# WL-BPF_L.net
KiCad netlist of a schematic drawn in Altium Designer
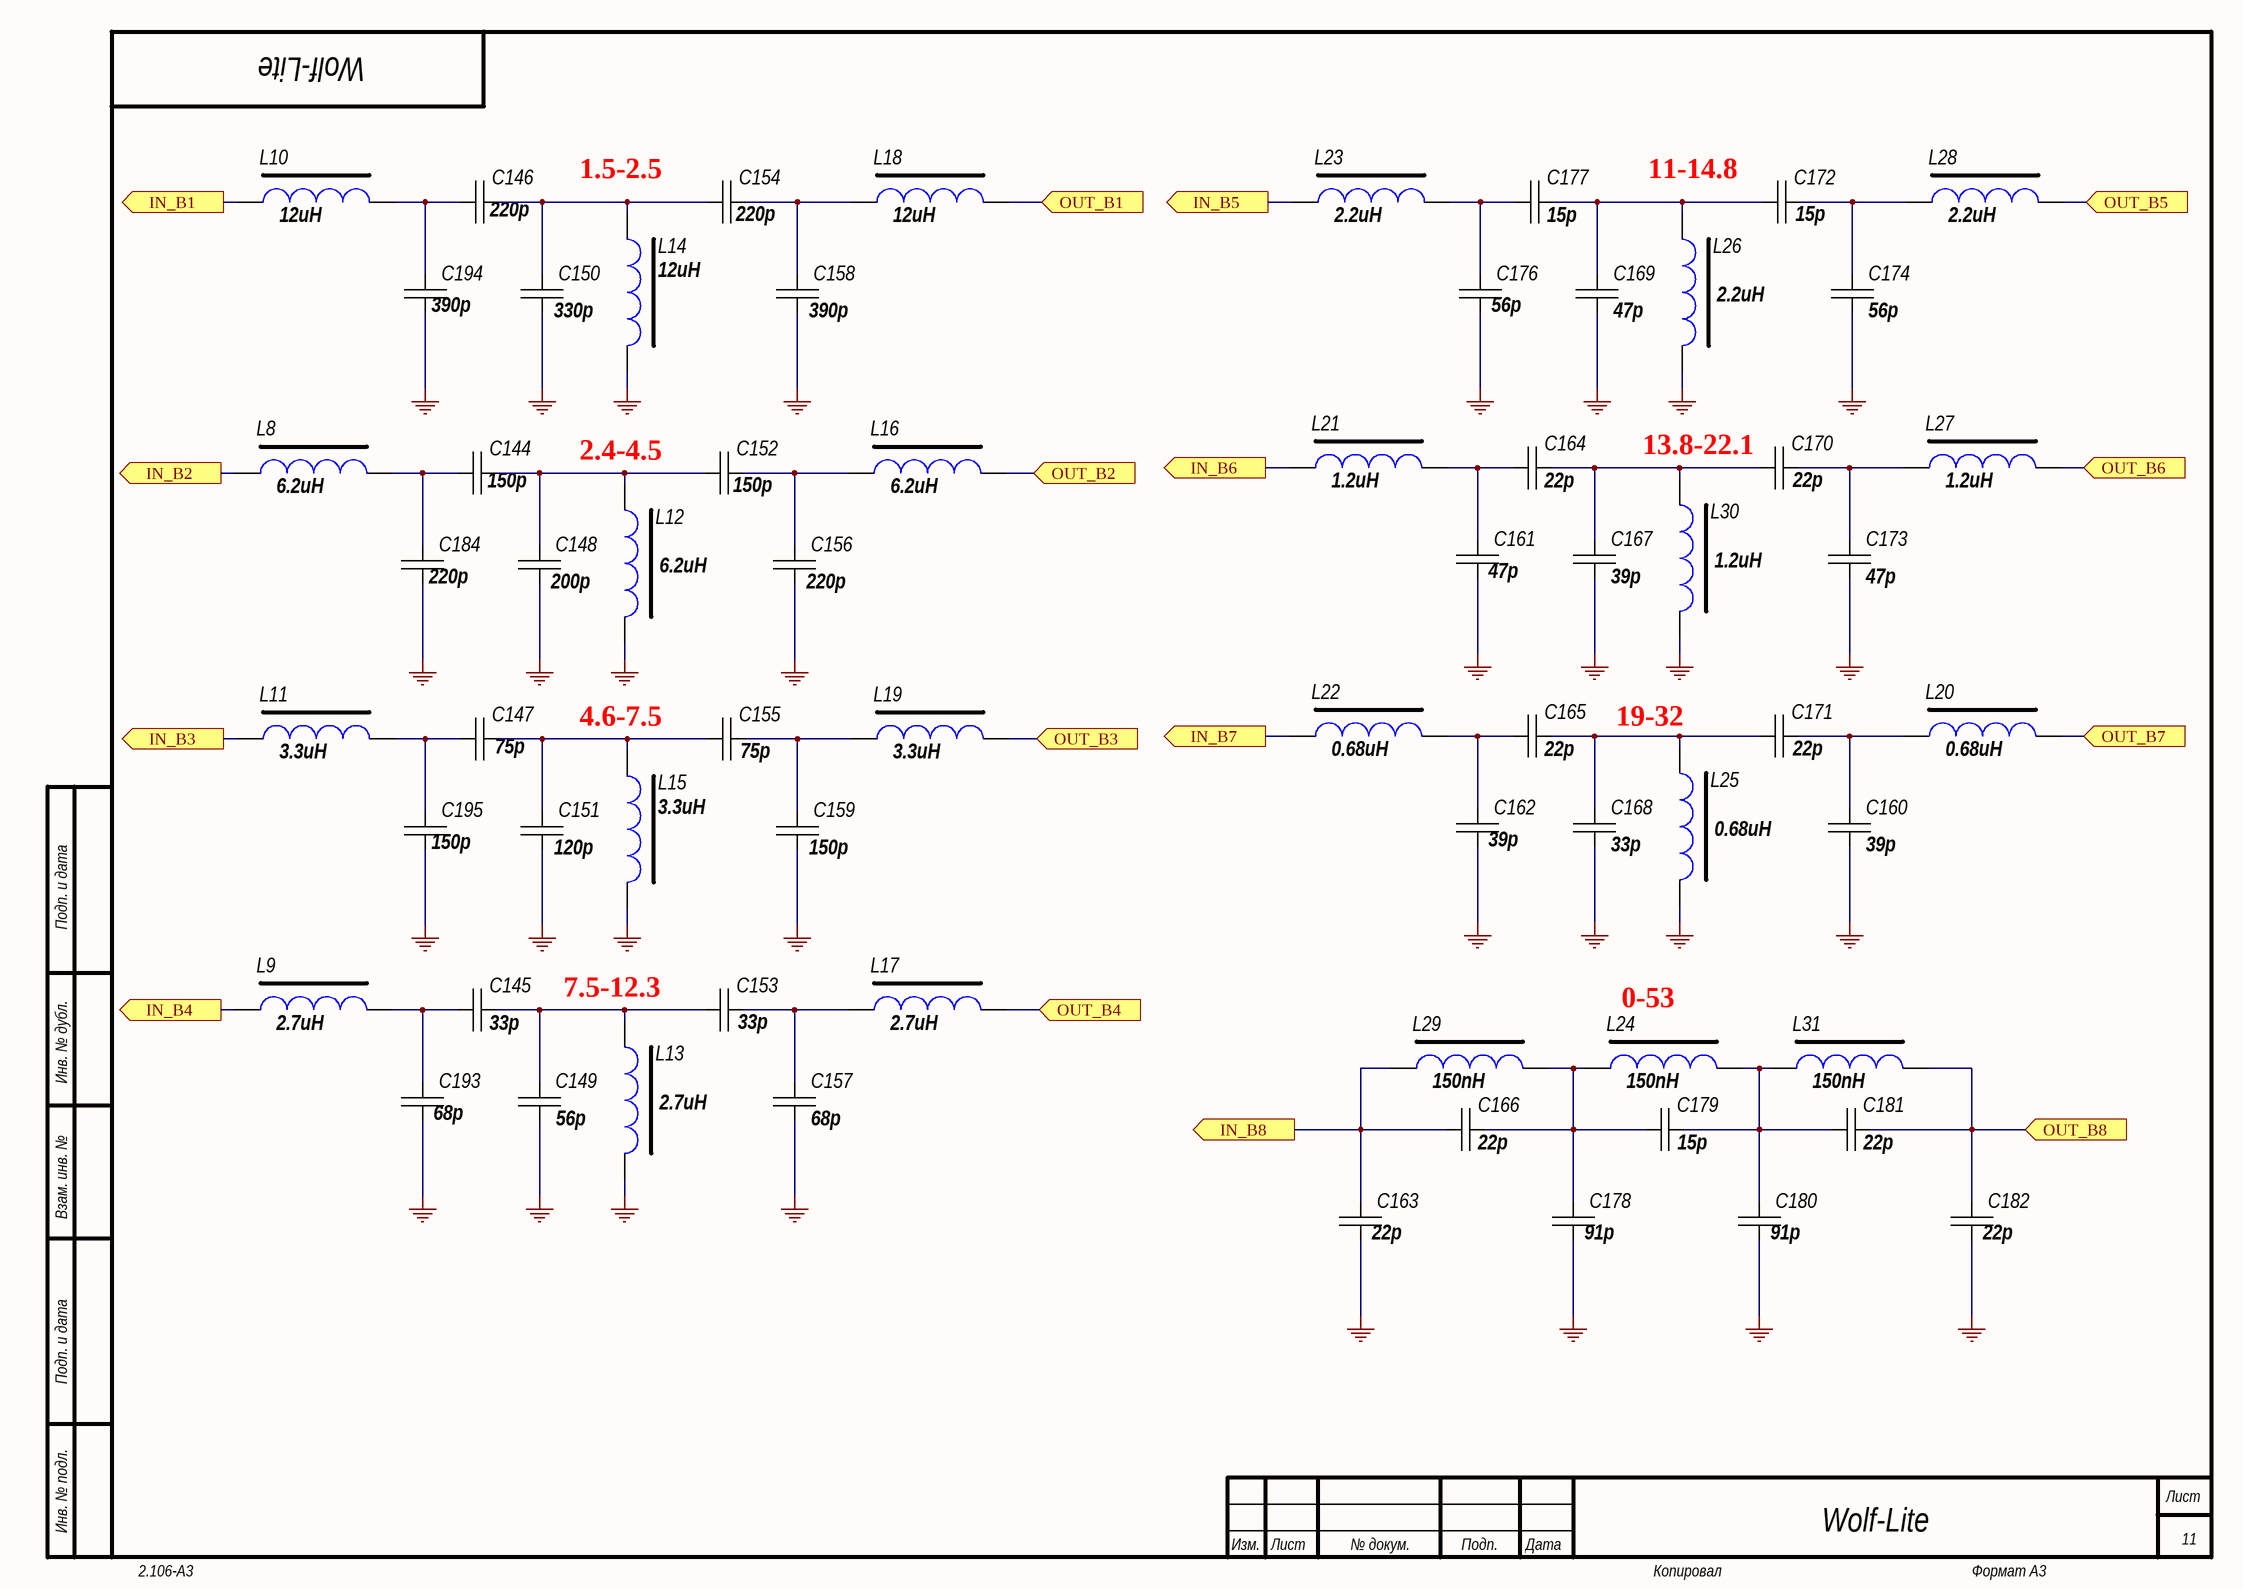
[diagram p0: WL-BPF_L.SchDoc]

(export (version "E")
  (design (tool "Eeschema 10.0.6"))
  (components
    (comp (ref "C144")
      (value "150p")
      (footprint "standard:CH0805C")
      (libsource (lib "Discrete") (part "Capacitor"))
    )
    (comp (ref "C145")
      (value "33p")
      (footprint "standard:CH0805C")
      (libsource (lib "Discrete") (part "Capacitor"))
    )
    (comp (ref "C146")
      (value "220p")
      (footprint "standard:CH0805C")
      (libsource (lib "Discrete") (part "Capacitor"))
    )
    (comp (ref "C147")
      (value "75p")
      (footprint "standard:CH0805C")
      (libsource (lib "Discrete") (part "Capacitor"))
    )
    (comp (ref "C148")
      (value "200p")
      (footprint "standard:CH0805C")
      (libsource (lib "Discrete") (part "Capacitor"))
    )
    (comp (ref "C149")
      (value "56p")
      (footprint "standard:CH0805C")
      (libsource (lib "Discrete") (part "Capacitor"))
    )
    (comp (ref "C150")
      (value "330p")
      (footprint "standard:CH0805C")
      (libsource (lib "Discrete") (part "Capacitor"))
    )
    (comp (ref "C151")
      (value "120p")
      (footprint "standard:CH0805C")
      (libsource (lib "Discrete") (part "Capacitor"))
    )
    (comp (ref "C152")
      (value "150p")
      (footprint "standard:CH0805C")
      (libsource (lib "Discrete") (part "Capacitor"))
    )
    (comp (ref "C153")
      (value "33p")
      (footprint "standard:CH0805C")
      (libsource (lib "Discrete") (part "Capacitor"))
    )
    (comp (ref "C154")
      (value "220p")
      (footprint "standard:CH0805C")
      (libsource (lib "Discrete") (part "Capacitor"))
    )
    (comp (ref "C155")
      (value "75p")
      (footprint "standard:CH0805C")
      (libsource (lib "Discrete") (part "Capacitor"))
    )
    (comp (ref "C156")
      (value "220p")
      (footprint "standard:CH0805C")
      (libsource (lib "Discrete") (part "Capacitor"))
    )
    (comp (ref "C157")
      (value "68p")
      (footprint "standard:CH0805C")
      (libsource (lib "Discrete") (part "Capacitor"))
    )
    (comp (ref "C158")
      (value "390p")
      (footprint "standard:CH0805C")
      (libsource (lib "Discrete") (part "Capacitor"))
    )
    (comp (ref "C159")
      (value "150p")
      (footprint "standard:CH0805C")
      (libsource (lib "Discrete") (part "Capacitor"))
    )
    (comp (ref "C160")
      (value "39p")
      (footprint "standard:CH0805C")
      (libsource (lib "Discrete") (part "Capacitor"))
    )
    (comp (ref "C161")
      (value "47p")
      (footprint "standard:CH0805C")
      (libsource (lib "Discrete") (part "Capacitor"))
    )
    (comp (ref "C162")
      (value "39p")
      (footprint "standard:CH0805C")
      (libsource (lib "Discrete") (part "Capacitor"))
    )
    (comp (ref "C163")
      (value "22p")
      (footprint "standard:CH0805C")
      (libsource (lib "Discrete") (part "Capacitor"))
    )
    (comp (ref "C164")
      (value "22p")
      (footprint "standard:CH0805C")
      (libsource (lib "Discrete") (part "Capacitor"))
    )
    (comp (ref "C165")
      (value "22p")
      (footprint "standard:CH0805C")
      (libsource (lib "Discrete") (part "Capacitor"))
    )
    (comp (ref "C166")
      (value "22p")
      (footprint "standard:CH0805C")
      (libsource (lib "Discrete") (part "Capacitor"))
    )
    (comp (ref "C167")
      (value "39p")
      (footprint "standard:CH0805C")
      (libsource (lib "Discrete") (part "Capacitor"))
    )
    (comp (ref "C168")
      (value "33p")
      (footprint "standard:CH0805C")
      (libsource (lib "Discrete") (part "Capacitor"))
    )
    (comp (ref "C169")
      (value "47p")
      (footprint "standard:CH0805C")
      (libsource (lib "Discrete") (part "Capacitor"))
    )
    (comp (ref "C170")
      (value "22p")
      (footprint "standard:CH0805C")
      (libsource (lib "Discrete") (part "Capacitor"))
    )
    (comp (ref "C171")
      (value "22p")
      (footprint "standard:CH0805C")
      (libsource (lib "Discrete") (part "Capacitor"))
    )
    (comp (ref "C172")
      (value "15p")
      (footprint "standard:CH0805C")
      (libsource (lib "Discrete") (part "Capacitor"))
    )
    (comp (ref "C173")
      (value "47p")
      (footprint "standard:CH0805C")
      (libsource (lib "Discrete") (part "Capacitor"))
    )
    (comp (ref "C174")
      (value "56p")
      (footprint "standard:CH0805C")
      (libsource (lib "Discrete") (part "Capacitor"))
    )
    (comp (ref "C176")
      (value "56p")
      (footprint "standard:CH0805C")
      (libsource (lib "Discrete") (part "Capacitor"))
    )
    (comp (ref "C177")
      (value "15p")
      (footprint "standard:CH0805C")
      (libsource (lib "Discrete") (part "Capacitor"))
    )
    (comp (ref "C178")
      (value "91p")
      (footprint "standard:CH0805C")
      (libsource (lib "Discrete") (part "Capacitor"))
    )
    (comp (ref "C179")
      (value "15p")
      (footprint "standard:CH0805C")
      (libsource (lib "Discrete") (part "Capacitor"))
    )
    (comp (ref "C180")
      (value "91p")
      (footprint "standard:CH0805C")
      (libsource (lib "Discrete") (part "Capacitor"))
    )
    (comp (ref "C181")
      (value "22p")
      (footprint "standard:CH0805C")
      (libsource (lib "Discrete") (part "Capacitor"))
    )
    (comp (ref "C182")
      (value "22p")
      (footprint "standard:CH0805C")
      (libsource (lib "Discrete") (part "Capacitor"))
    )
    (comp (ref "C184")
      (value "220p")
      (footprint "standard:CH0805C")
      (libsource (lib "Discrete") (part "Capacitor"))
    )
    (comp (ref "C193")
      (value "68p")
      (footprint "standard:CH0805C")
      (libsource (lib "Discrete") (part "Capacitor"))
    )
    (comp (ref "C194")
      (value "390p")
      (footprint "standard:CH0805C")
      (libsource (lib "Discrete") (part "Capacitor"))
    )
    (comp (ref "C195")
      (value "150p")
      (footprint "standard:CH0805C")
      (libsource (lib "Discrete") (part "Capacitor"))
    )
    (comp (ref "L8") (value "6.2uH") (footprint "L1210") (libsource (lib "Transformers") (part "TRANS")))
    (comp (ref "L9") (value "2.7uH") (footprint "L1210") (libsource (lib "Transformers") (part "TRANS")))
    (comp (ref "L10") (value "12uH") (footprint "L1210") (libsource (lib "Transformers") (part "TRANS")))
    (comp (ref "L11") (value "3.3uH") (footprint "L1210") (libsource (lib "Transformers") (part "TRANS")))
    (comp (ref "L12") (value "6.2uH") (footprint "L1210") (libsource (lib "") (part "TRANS_1")))
    (comp (ref "L13") (value "2.7uH") (footprint "L1210") (libsource (lib "") (part "TRANS_1")))
    (comp (ref "L14") (value "12uH") (footprint "L1210") (libsource (lib "") (part "TRANS_1")))
    (comp (ref "L15") (value "3.3uH") (footprint "L1210") (libsource (lib "") (part "TRANS_1")))
    (comp (ref "L16") (value "6.2uH") (footprint "L1210") (libsource (lib "Transformers") (part "TRANS")))
    (comp (ref "L17") (value "2.7uH") (footprint "L1210") (libsource (lib "Transformers") (part "TRANS")))
    (comp (ref "L18") (value "12uH") (footprint "L1210") (libsource (lib "Transformers") (part "TRANS")))
    (comp (ref "L19") (value "3.3uH") (footprint "L1210") (libsource (lib "Transformers") (part "TRANS")))
    (comp (ref "L20") (value "0.68uH") (footprint "L1210") (libsource (lib "Transformers") (part "TRANS")))
    (comp (ref "L21") (value "1.2uH") (footprint "L1210") (libsource (lib "Transformers") (part "TRANS")))
    (comp (ref "L22") (value "0.68uH") (footprint "L1210") (libsource (lib "Transformers") (part "TRANS")))
    (comp (ref "L23") (value "2.2uH") (footprint "L1210") (libsource (lib "Transformers") (part "TRANS")))
    (comp (ref "L24") (value "150nH") (footprint "L1210") (libsource (lib "Transformers") (part "TRANS")))
    (comp (ref "L25") (value "0.68uH") (footprint "L1210") (libsource (lib "") (part "TRANS_1")))
    (comp (ref "L26") (value "2.2uH") (footprint "L1210") (libsource (lib "") (part "TRANS_1")))
    (comp (ref "L27") (value "1.2uH") (footprint "L1210") (libsource (lib "Transformers") (part "TRANS")))
    (comp (ref "L28") (value "2.2uH") (footprint "L1210") (libsource (lib "Transformers") (part "TRANS")))
    (comp (ref "L29") (value "150nH") (footprint "L1210") (libsource (lib "Transformers") (part "TRANS")))
    (comp (ref "L30") (value "1.2uH") (footprint "L1210") (libsource (lib "") (part "TRANS_1")))
    (comp (ref "L31") (value "150nH") (footprint "L1210") (libsource (lib "Transformers") (part "TRANS")))
  )
  (nets
    (net (code "1") (name "/IN_B1") (class "Default")
      (node (ref "L10") (pin "1") (pinfunction "1_1") (pintype "power_in"))
    )
    (net (code "2") (name "/IN_B2") (class "Default")
      (node (ref "L8") (pin "1") (pinfunction "1_1") (pintype "power_in"))
    )
    (net (code "3") (name "/IN_B3") (class "Default")
      (node (ref "L11") (pin "1") (pinfunction "1_1") (pintype "power_in"))
    )
    (net (code "4") (name "/IN_B4") (class "Default")
      (node (ref "L9") (pin "1") (pinfunction "1_1") (pintype "power_in"))
    )
    (net (code "5") (name "/IN_B5") (class "Default")
      (node (ref "L23") (pin "1") (pinfunction "1_1") (pintype "power_in"))
    )
    (net (code "6") (name "/IN_B6") (class "Default")
      (node (ref "L21") (pin "1") (pinfunction "1_1") (pintype "power_in"))
    )
    (net (code "7") (name "/IN_B7") (class "Default")
      (node (ref "L22") (pin "1") (pinfunction "1_1") (pintype "power_in"))
    )
    (net (code "8") (name "/IN_B8") (class "Default")
      (node (ref "C163") (pin "2") (pinfunction "2_2") (pintype "power_in"))
      (node (ref "C166") (pin "1") (pinfunction "1_1") (pintype "power_in"))
      (node (ref "L29") (pin "1") (pinfunction "1_1") (pintype "power_in"))
    )
    (net (code "9") (name "/OUT_B1") (class "Default")
      (node (ref "L18") (pin "2") (pinfunction "2_2") (pintype "power_in"))
    )
    (net (code "10") (name "/OUT_B2") (class "Default")
      (node (ref "L16") (pin "2") (pinfunction "2_2") (pintype "power_in"))
    )
    (net (code "11") (name "/OUT_B3") (class "Default")
      (node (ref "L19") (pin "2") (pinfunction "2_2") (pintype "power_in"))
    )
    (net (code "12") (name "/OUT_B4") (class "Default")
      (node (ref "L17") (pin "2") (pinfunction "2_2") (pintype "power_in"))
    )
    (net (code "13") (name "/OUT_B5") (class "Default")
      (node (ref "L28") (pin "2") (pinfunction "2_2") (pintype "power_in"))
    )
    (net (code "14") (name "/OUT_B6") (class "Default")
      (node (ref "L27") (pin "2") (pinfunction "2_2") (pintype "power_in"))
    )
    (net (code "15") (name "/OUT_B7") (class "Default")
      (node (ref "L20") (pin "2") (pinfunction "2_2") (pintype "power_in"))
    )
    (net (code "16") (name "/OUT_B8") (class "Default")
      (node (ref "C181") (pin "2") (pinfunction "2_2") (pintype "power_in"))
      (node (ref "C182") (pin "2") (pinfunction "2_2") (pintype "power_in"))
      (node (ref "L31") (pin "2") (pinfunction "2_2") (pintype "power_in"))
    )
    (net (code "17") (name "GND") (class "Default")
      (node (ref "C148") (pin "1") (pinfunction "1_1") (pintype "power_in"))
      (node (ref "C149") (pin "1") (pinfunction "1_1") (pintype "power_in"))
      (node (ref "C150") (pin "1") (pinfunction "1_1") (pintype "power_in"))
      (node (ref "C151") (pin "1") (pinfunction "1_1") (pintype "power_in"))
      (node (ref "C156") (pin "1") (pinfunction "1_1") (pintype "power_in"))
      (node (ref "C157") (pin "1") (pinfunction "1_1") (pintype "power_in"))
      (node (ref "C158") (pin "1") (pinfunction "1_1") (pintype "power_in"))
      (node (ref "C159") (pin "1") (pinfunction "1_1") (pintype "power_in"))
      (node (ref "C160") (pin "1") (pinfunction "1_1") (pintype "power_in"))
      (node (ref "C161") (pin "1") (pinfunction "1_1") (pintype "power_in"))
      (node (ref "C162") (pin "1") (pinfunction "1_1") (pintype "power_in"))
      (node (ref "C163") (pin "1") (pinfunction "1_1") (pintype "power_in"))
      (node (ref "C167") (pin "1") (pinfunction "1_1") (pintype "power_in"))
      (node (ref "C168") (pin "1") (pinfunction "1_1") (pintype "power_in"))
      (node (ref "C169") (pin "1") (pinfunction "1_1") (pintype "power_in"))
      (node (ref "C173") (pin "1") (pinfunction "1_1") (pintype "power_in"))
      (node (ref "C174") (pin "1") (pinfunction "1_1") (pintype "power_in"))
      (node (ref "C176") (pin "1") (pinfunction "1_1") (pintype "power_in"))
      (node (ref "C178") (pin "1") (pinfunction "1_1") (pintype "power_in"))
      (node (ref "C180") (pin "1") (pinfunction "1_1") (pintype "power_in"))
      (node (ref "C182") (pin "1") (pinfunction "1_1") (pintype "power_in"))
      (node (ref "C184") (pin "1") (pinfunction "1_1") (pintype "power_in"))
      (node (ref "C193") (pin "1") (pinfunction "1_1") (pintype "power_in"))
      (node (ref "C194") (pin "1") (pinfunction "1_1") (pintype "power_in"))
      (node (ref "C195") (pin "1") (pinfunction "1_1") (pintype "power_in"))
      (node (ref "L12") (pin "1") (pinfunction "1_1") (pintype "power_in"))
      (node (ref "L13") (pin "1") (pinfunction "1_1") (pintype "power_in"))
      (node (ref "L14") (pin "1") (pinfunction "1_1") (pintype "power_in"))
      (node (ref "L15") (pin "1") (pinfunction "1_1") (pintype "power_in"))
      (node (ref "L25") (pin "1") (pinfunction "1_1") (pintype "power_in"))
      (node (ref "L26") (pin "1") (pinfunction "1_1") (pintype "power_in"))
      (node (ref "L30") (pin "1") (pinfunction "1_1") (pintype "power_in"))
    )
    (net (code "18") (name "Net-(C144-Pad1)") (class "Default")
      (node (ref "C144") (pin "1") (pinfunction "1_1") (pintype "power_in"))
      (node (ref "C184") (pin "2") (pinfunction "2_2") (pintype "power_in"))
      (node (ref "L8") (pin "2") (pinfunction "2_2") (pintype "power_in"))
    )
    (net (code "19") (name "Net-(C144-Pad2)") (class "Default")
      (node (ref "C144") (pin "2") (pinfunction "2_2") (pintype "power_in"))
      (node (ref "C148") (pin "2") (pinfunction "2_2") (pintype "power_in"))
      (node (ref "C152") (pin "1") (pinfunction "1_1") (pintype "power_in"))
      (node (ref "L12") (pin "2") (pinfunction "2_2") (pintype "power_in"))
    )
    (net (code "20") (name "Net-(C145-Pad1)") (class "Default")
      (node (ref "C145") (pin "1") (pinfunction "1_1") (pintype "power_in"))
      (node (ref "C193") (pin "2") (pinfunction "2_2") (pintype "power_in"))
      (node (ref "L9") (pin "2") (pinfunction "2_2") (pintype "power_in"))
    )
    (net (code "21") (name "Net-(C145-Pad2)") (class "Default")
      (node (ref "C145") (pin "2") (pinfunction "2_2") (pintype "power_in"))
      (node (ref "C149") (pin "2") (pinfunction "2_2") (pintype "power_in"))
      (node (ref "C153") (pin "1") (pinfunction "1_1") (pintype "power_in"))
      (node (ref "L13") (pin "2") (pinfunction "2_2") (pintype "power_in"))
    )
    (net (code "22") (name "Net-(C146-Pad1)") (class "Default")
      (node (ref "C146") (pin "1") (pinfunction "1_1") (pintype "power_in"))
      (node (ref "C194") (pin "2") (pinfunction "2_2") (pintype "power_in"))
      (node (ref "L10") (pin "2") (pinfunction "2_2") (pintype "power_in"))
    )
    (net (code "23") (name "Net-(C146-Pad2)") (class "Default")
      (node (ref "C146") (pin "2") (pinfunction "2_2") (pintype "power_in"))
      (node (ref "C150") (pin "2") (pinfunction "2_2") (pintype "power_in"))
      (node (ref "C154") (pin "1") (pinfunction "1_1") (pintype "power_in"))
      (node (ref "L14") (pin "2") (pinfunction "2_2") (pintype "power_in"))
    )
    (net (code "24") (name "Net-(C147-Pad1)") (class "Default")
      (node (ref "C147") (pin "1") (pinfunction "1_1") (pintype "power_in"))
      (node (ref "C195") (pin "2") (pinfunction "2_2") (pintype "power_in"))
      (node (ref "L11") (pin "2") (pinfunction "2_2") (pintype "power_in"))
    )
    (net (code "25") (name "Net-(C147-Pad2)") (class "Default")
      (node (ref "C147") (pin "2") (pinfunction "2_2") (pintype "power_in"))
      (node (ref "C151") (pin "2") (pinfunction "2_2") (pintype "power_in"))
      (node (ref "C155") (pin "1") (pinfunction "1_1") (pintype "power_in"))
      (node (ref "L15") (pin "2") (pinfunction "2_2") (pintype "power_in"))
    )
    (net (code "26") (name "Net-(C152-Pad2)") (class "Default")
      (node (ref "C152") (pin "2") (pinfunction "2_2") (pintype "power_in"))
      (node (ref "C156") (pin "2") (pinfunction "2_2") (pintype "power_in"))
      (node (ref "L16") (pin "1") (pinfunction "1_1") (pintype "power_in"))
    )
    (net (code "27") (name "Net-(C153-Pad2)") (class "Default")
      (node (ref "C153") (pin "2") (pinfunction "2_2") (pintype "power_in"))
      (node (ref "C157") (pin "2") (pinfunction "2_2") (pintype "power_in"))
      (node (ref "L17") (pin "1") (pinfunction "1_1") (pintype "power_in"))
    )
    (net (code "28") (name "Net-(C154-Pad2)") (class "Default")
      (node (ref "C154") (pin "2") (pinfunction "2_2") (pintype "power_in"))
      (node (ref "C158") (pin "2") (pinfunction "2_2") (pintype "power_in"))
      (node (ref "L18") (pin "1") (pinfunction "1_1") (pintype "power_in"))
    )
    (net (code "29") (name "Net-(C155-Pad2)") (class "Default")
      (node (ref "C155") (pin "2") (pinfunction "2_2") (pintype "power_in"))
      (node (ref "C159") (pin "2") (pinfunction "2_2") (pintype "power_in"))
      (node (ref "L19") (pin "1") (pinfunction "1_1") (pintype "power_in"))
    )
    (net (code "30") (name "Net-(C160-Pad2)") (class "Default")
      (node (ref "C160") (pin "2") (pinfunction "2_2") (pintype "power_in"))
      (node (ref "C171") (pin "2") (pinfunction "2_2") (pintype "power_in"))
      (node (ref "L20") (pin "1") (pinfunction "1_1") (pintype "power_in"))
    )
    (net (code "31") (name "Net-(C161-Pad2)") (class "Default")
      (node (ref "C161") (pin "2") (pinfunction "2_2") (pintype "power_in"))
      (node (ref "C164") (pin "1") (pinfunction "1_1") (pintype "power_in"))
      (node (ref "L21") (pin "2") (pinfunction "2_2") (pintype "power_in"))
    )
    (net (code "32") (name "Net-(C162-Pad2)") (class "Default")
      (node (ref "C162") (pin "2") (pinfunction "2_2") (pintype "power_in"))
      (node (ref "C165") (pin "1") (pinfunction "1_1") (pintype "power_in"))
      (node (ref "L22") (pin "2") (pinfunction "2_2") (pintype "power_in"))
    )
    (net (code "33") (name "Net-(C164-Pad2)") (class "Default")
      (node (ref "C164") (pin "2") (pinfunction "2_2") (pintype "power_in"))
      (node (ref "C167") (pin "2") (pinfunction "2_2") (pintype "power_in"))
      (node (ref "C170") (pin "1") (pinfunction "1_1") (pintype "power_in"))
      (node (ref "L30") (pin "2") (pinfunction "2_2") (pintype "power_in"))
    )
    (net (code "34") (name "Net-(C165-Pad2)") (class "Default")
      (node (ref "C165") (pin "2") (pinfunction "2_2") (pintype "power_in"))
      (node (ref "C168") (pin "2") (pinfunction "2_2") (pintype "power_in"))
      (node (ref "C171") (pin "1") (pinfunction "1_1") (pintype "power_in"))
      (node (ref "L25") (pin "2") (pinfunction "2_2") (pintype "power_in"))
    )
    (net (code "35") (name "Net-(C166-Pad2)") (class "Default")
      (node (ref "C166") (pin "2") (pinfunction "2_2") (pintype "power_in"))
      (node (ref "C178") (pin "2") (pinfunction "2_2") (pintype "power_in"))
      (node (ref "C179") (pin "1") (pinfunction "1_1") (pintype "power_in"))
      (node (ref "L24") (pin "1") (pinfunction "1_1") (pintype "power_in"))
      (node (ref "L29") (pin "2") (pinfunction "2_2") (pintype "power_in"))
    )
    (net (code "36") (name "Net-(C169-Pad2)") (class "Default")
      (node (ref "C169") (pin "2") (pinfunction "2_2") (pintype "power_in"))
      (node (ref "C172") (pin "1") (pinfunction "1_1") (pintype "power_in"))
      (node (ref "C177") (pin "2") (pinfunction "2_2") (pintype "power_in"))
      (node (ref "L26") (pin "2") (pinfunction "2_2") (pintype "power_in"))
    )
    (net (code "37") (name "Net-(C170-Pad2)") (class "Default")
      (node (ref "C170") (pin "2") (pinfunction "2_2") (pintype "power_in"))
      (node (ref "C173") (pin "2") (pinfunction "2_2") (pintype "power_in"))
      (node (ref "L27") (pin "1") (pinfunction "1_1") (pintype "power_in"))
    )
    (net (code "38") (name "Net-(C172-Pad2)") (class "Default")
      (node (ref "C172") (pin "2") (pinfunction "2_2") (pintype "power_in"))
      (node (ref "C174") (pin "2") (pinfunction "2_2") (pintype "power_in"))
      (node (ref "L28") (pin "1") (pinfunction "1_1") (pintype "power_in"))
    )
    (net (code "39") (name "Net-(C176-Pad2)") (class "Default")
      (node (ref "C176") (pin "2") (pinfunction "2_2") (pintype "power_in"))
      (node (ref "C177") (pin "1") (pinfunction "1_1") (pintype "power_in"))
      (node (ref "L23") (pin "2") (pinfunction "2_2") (pintype "power_in"))
    )
    (net (code "40") (name "Net-(C179-Pad2)") (class "Default")
      (node (ref "C179") (pin "2") (pinfunction "2_2") (pintype "power_in"))
      (node (ref "C180") (pin "2") (pinfunction "2_2") (pintype "power_in"))
      (node (ref "C181") (pin "1") (pinfunction "1_1") (pintype "power_in"))
      (node (ref "L24") (pin "2") (pinfunction "2_2") (pintype "power_in"))
      (node (ref "L31") (pin "1") (pinfunction "1_1") (pintype "power_in"))
    )
  )
)
